# attiniest85-display-shield-mk-1_0.net
KiCad netlist of a schematic drawn in EAGLE
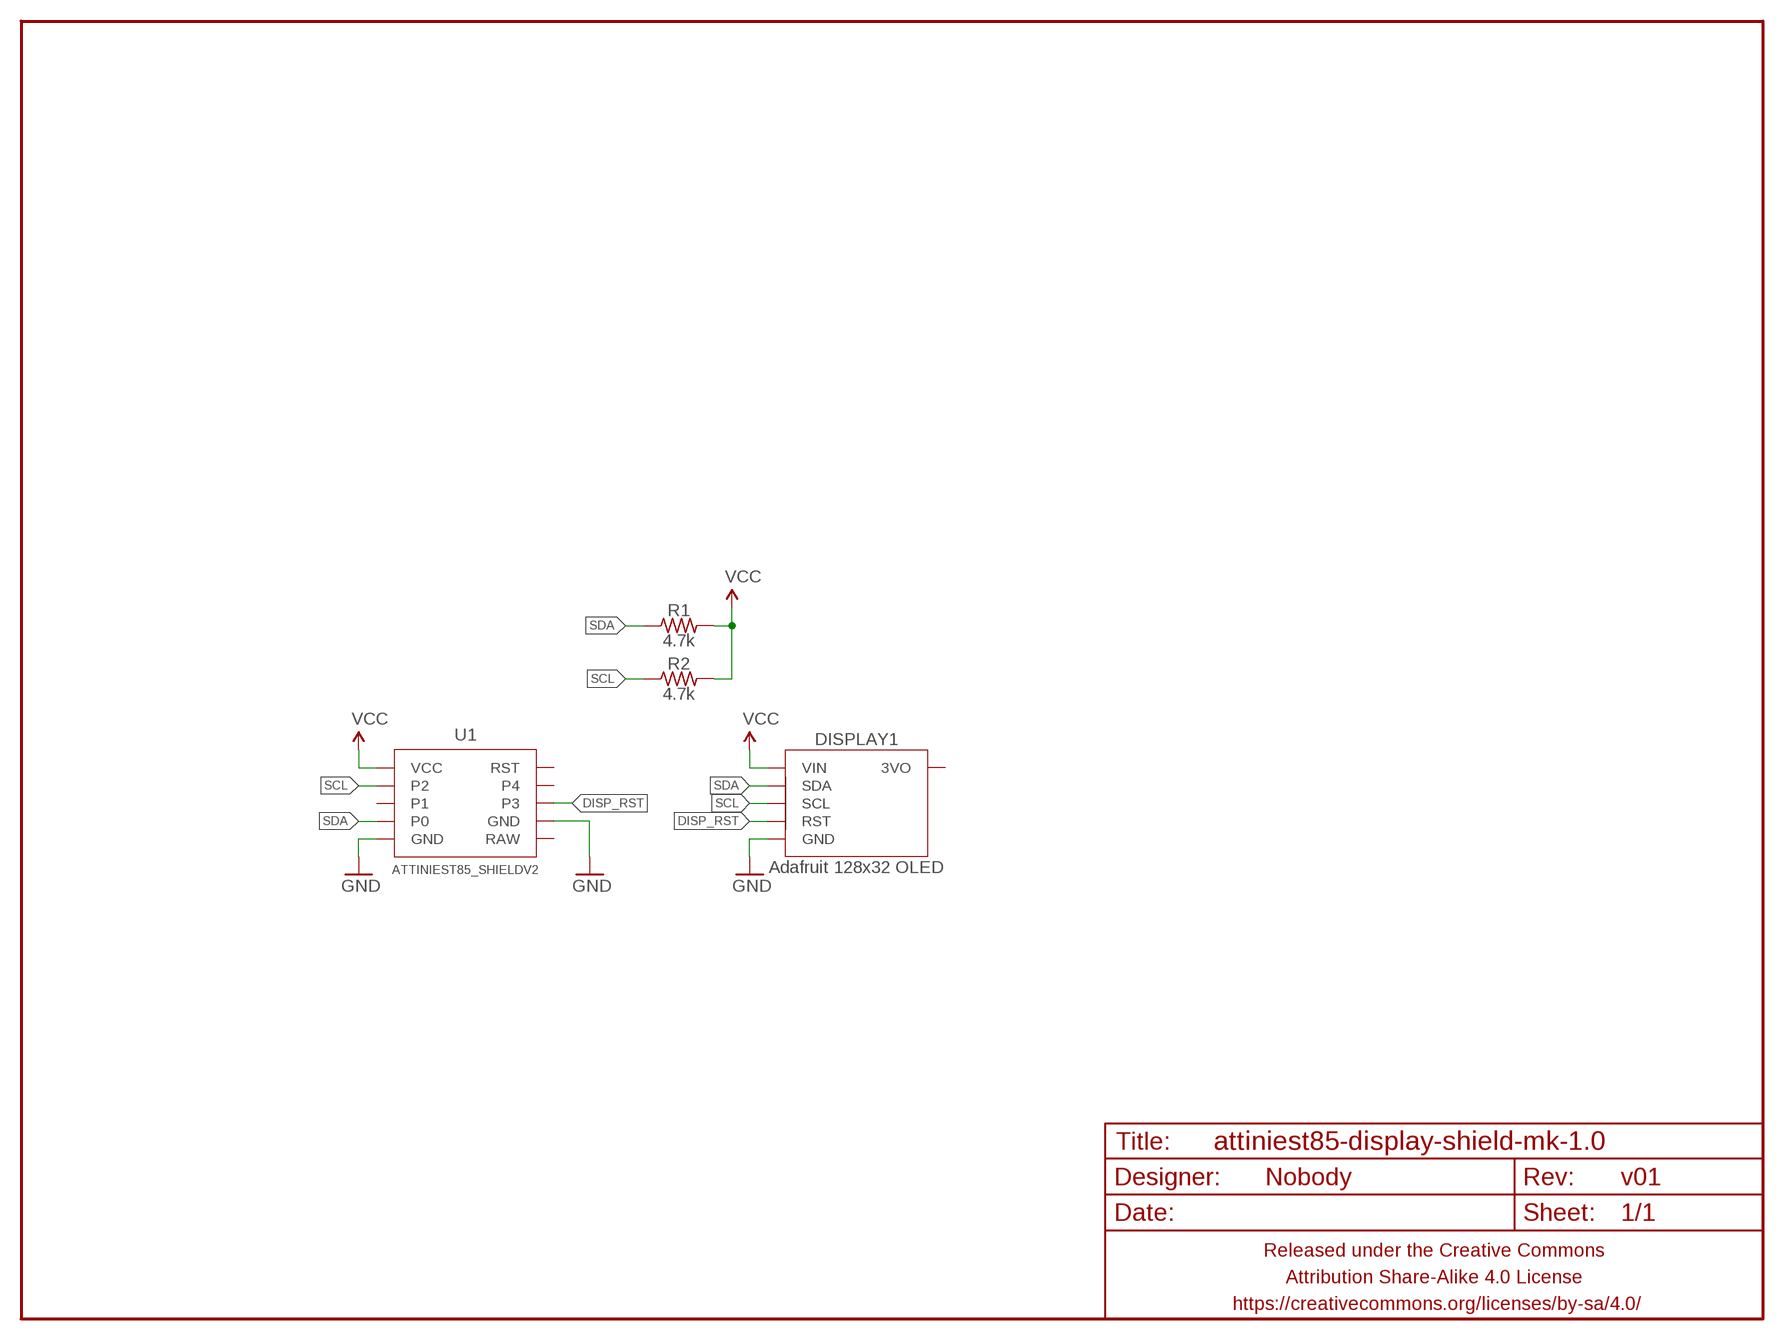
[diagram p0: schematic, sheet 1]

(export (version "E")
  (design (tool "Eeschema 10.0.6"))
  (components
    (comp (ref "DISPLAY1")
      (value "Adafruit 128x32 OLED")
      (footprint "eagle-import:ADAFRUIT_128X32_OLED_I2C_CLOSER_NOHOLES")
      (libsource (lib "eagle-import") (part "ADAFRUIT_128X32_OLED_I2CNOHOLES"))
    )
    (comp (ref "FRAME1")
      (value "FRAME-LETTERNO_PACKAGE")
      (footprint "eagle-import:DUMMY")
      (fields (field (name "DESIGNER") "Nobody"))
      (libsource (lib "eagle-import") (part "FRAME-LETTERNO_PACKAGE"))
    )
    (comp (ref "R1")
      (value "4.7k")
      (footprint "eagle-import:RESISTOR-AXIAL-PTH-7.62MM")
      (libsource (lib "eagle-import") (part "RESISTORPTH-AXIAL-7.62MM"))
    )
    (comp (ref "R2")
      (value "4.7k")
      (footprint "eagle-import:RESISTOR-AXIAL-PTH-7.62MM")
      (libsource (lib "eagle-import") (part "RESISTORPTH-AXIAL-7.62MM"))
    )
    (comp (ref "U1")
      (value "ATTINIEST85_SHIELDV2")
      (footprint "eagle-import:ATTINIEST85_SHIELD_V2")
      (libsource (lib "eagle-import") (part "ATTINIEST85_SHIELDV2"))
    )
  )
  (nets
    (net (code "1") (name "DISP_RST") (class "Default")
      (node (ref "DISPLAY1") (pin "RST") (pinfunction "RST_RST") (pintype "bidirectional"))
      (node (ref "U1") (pin "3") (pinfunction "P3_3") (pintype "bidirectional"))
    )
    (net (code "2") (name "GND") (class "Default")
      (node (ref "DISPLAY1") (pin "GND") (pinfunction "GND_GND") (pintype "bidirectional"))
      (node (ref "U1") (pin "GND@1") (pinfunction "GND_GND@1") (pintype "bidirectional"))
      (node (ref "U1") (pin "GND@2") (pinfunction "GND_GND@2") (pintype "bidirectional"))
    )
    (net (code "3") (name "SCL") (class "Default")
      (node (ref "DISPLAY1") (pin "SCL") (pinfunction "SCL_SCL") (pintype "bidirectional"))
      (node (ref "R2") (pin "P$1") (pinfunction "1_P$1") (pintype "passive"))
      (node (ref "U1") (pin "2") (pinfunction "P2_2") (pintype "bidirectional"))
    )
    (net (code "4") (name "SDA") (class "Default")
      (node (ref "DISPLAY1") (pin "SDA") (pinfunction "SDA_SDA") (pintype "bidirectional"))
      (node (ref "R1") (pin "P$1") (pinfunction "1_P$1") (pintype "passive"))
      (node (ref "U1") (pin "0") (pinfunction "P0_0") (pintype "bidirectional"))
    )
    (net (code "5") (name "VCC") (class "Default")
      (node (ref "DISPLAY1") (pin "VIN") (pinfunction "VIN_VIN") (pintype "bidirectional"))
      (node (ref "R1") (pin "P$2") (pinfunction "2_P$2") (pintype "passive"))
      (node (ref "R2") (pin "P$2") (pinfunction "2_P$2") (pintype "passive"))
      (node (ref "U1") (pin "VCC") (pinfunction "VCC_VCC") (pintype "bidirectional"))
    )
    (net (code "6") (name "unconnected-(DISPLAY1-Pad3VO)") (class "Default")
      (node (ref "DISPLAY1") (pin "3VO") (pinfunction "3VO_3VO") (pintype "bidirectional"))
    )
    (net (code "7") (name "unconnected-(U1-P1-Pad1)") (class "Default")
      (node (ref "U1") (pin "1") (pinfunction "P1_1") (pintype "bidirectional"))
    )
    (net (code "8") (name "unconnected-(U1-P4-Pad4)") (class "Default")
      (node (ref "U1") (pin "4") (pinfunction "P4_4") (pintype "bidirectional"))
    )
    (net (code "9") (name "unconnected-(U1-PadRAW)") (class "Default")
      (node (ref "U1") (pin "RAW") (pinfunction "RAW_RAW") (pintype "bidirectional"))
    )
    (net (code "10") (name "unconnected-(U1-PadRST)") (class "Default")
      (node (ref "U1") (pin "RST") (pinfunction "RST_RST") (pintype "bidirectional"))
    )
  )
)
